# zynqBoard.net
KiCad netlist of a schematic drawn in Altium Designer
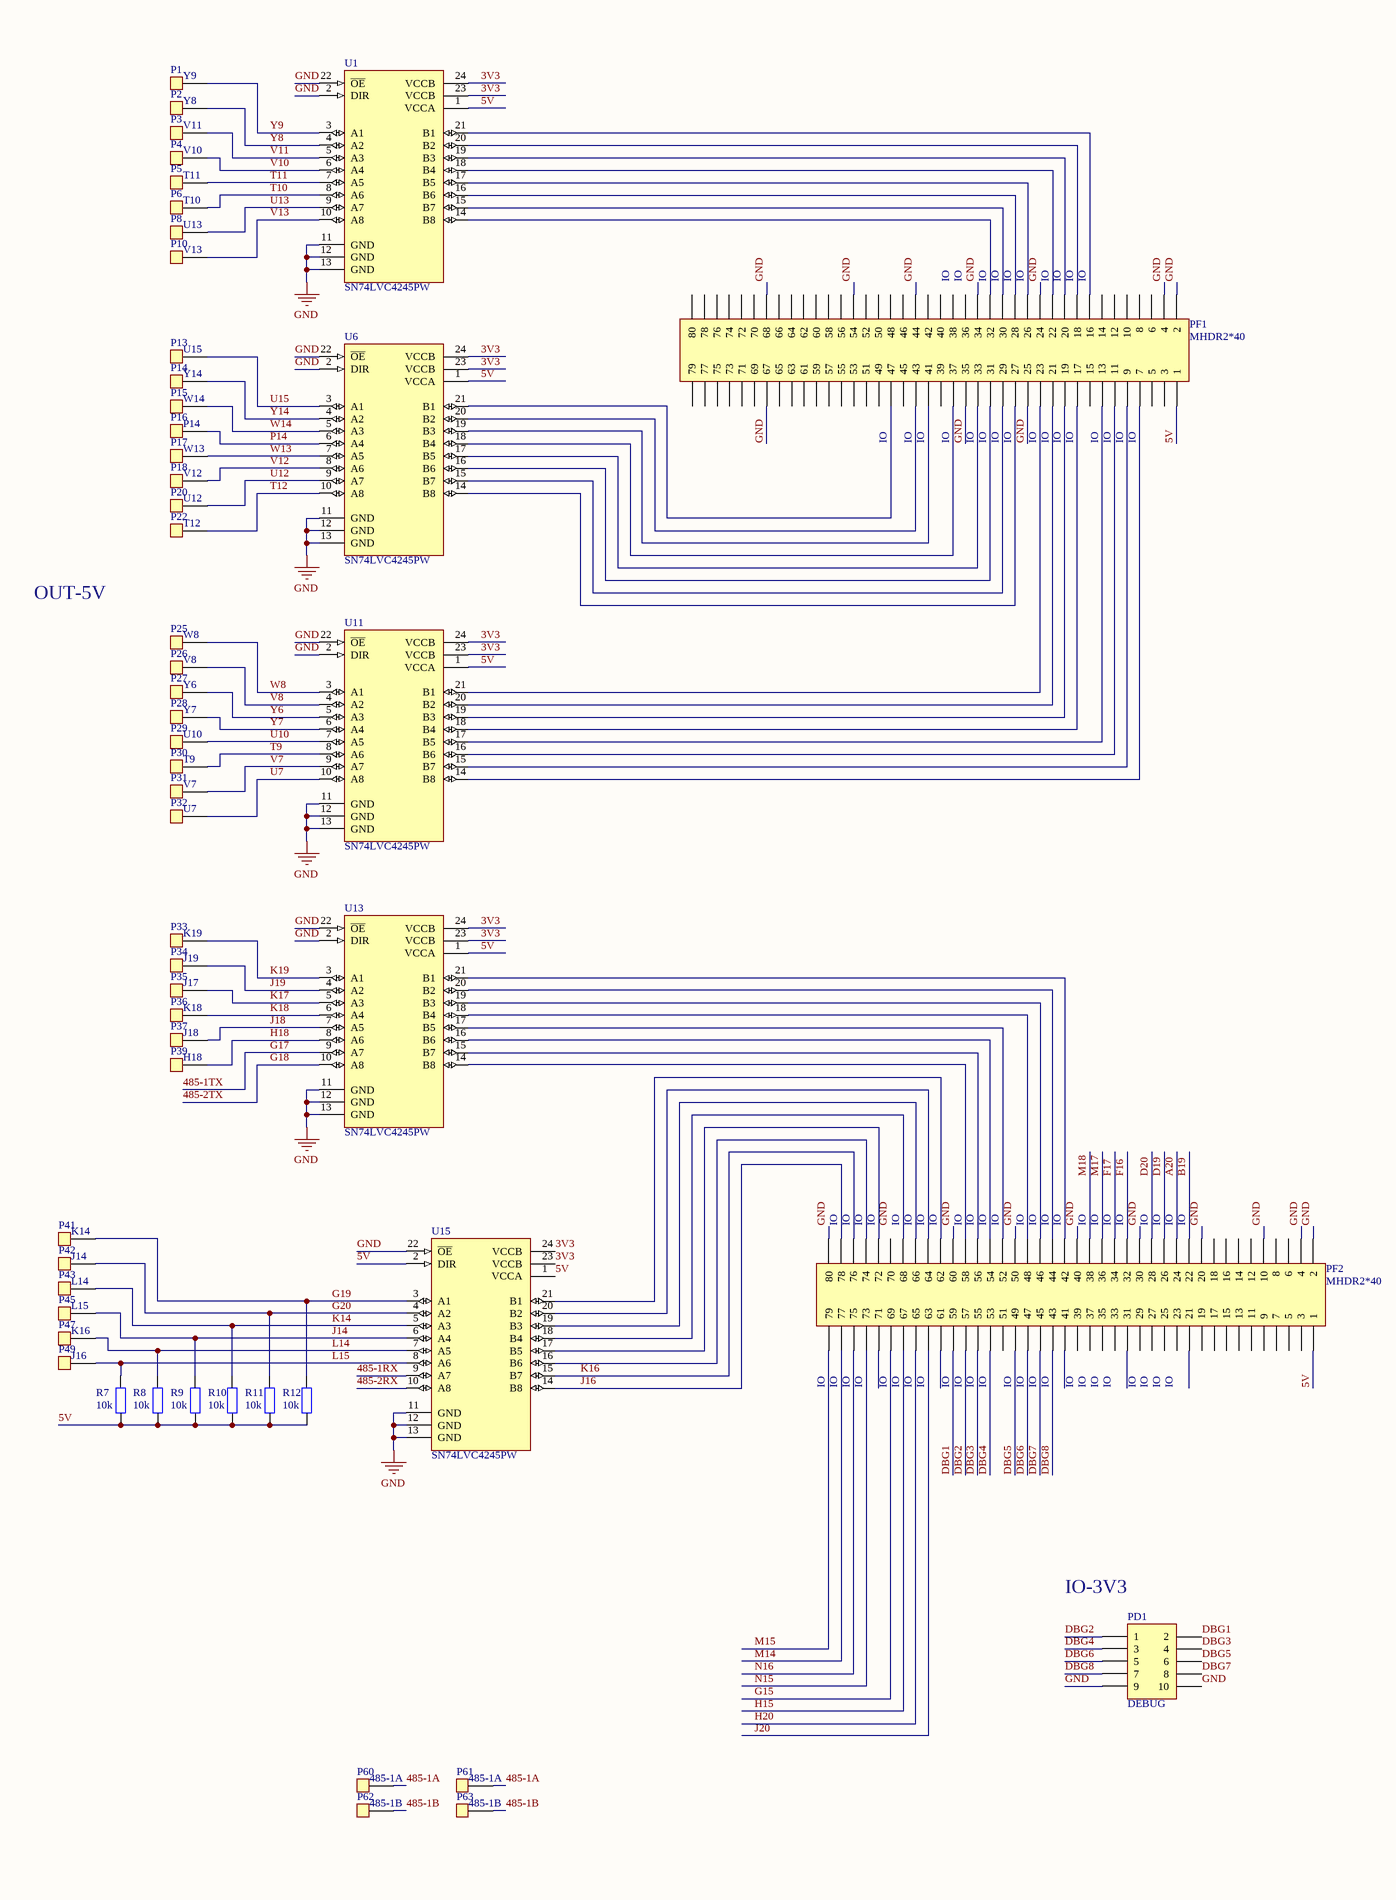
[diagram p0: zynqBoard.SchDoc, left]
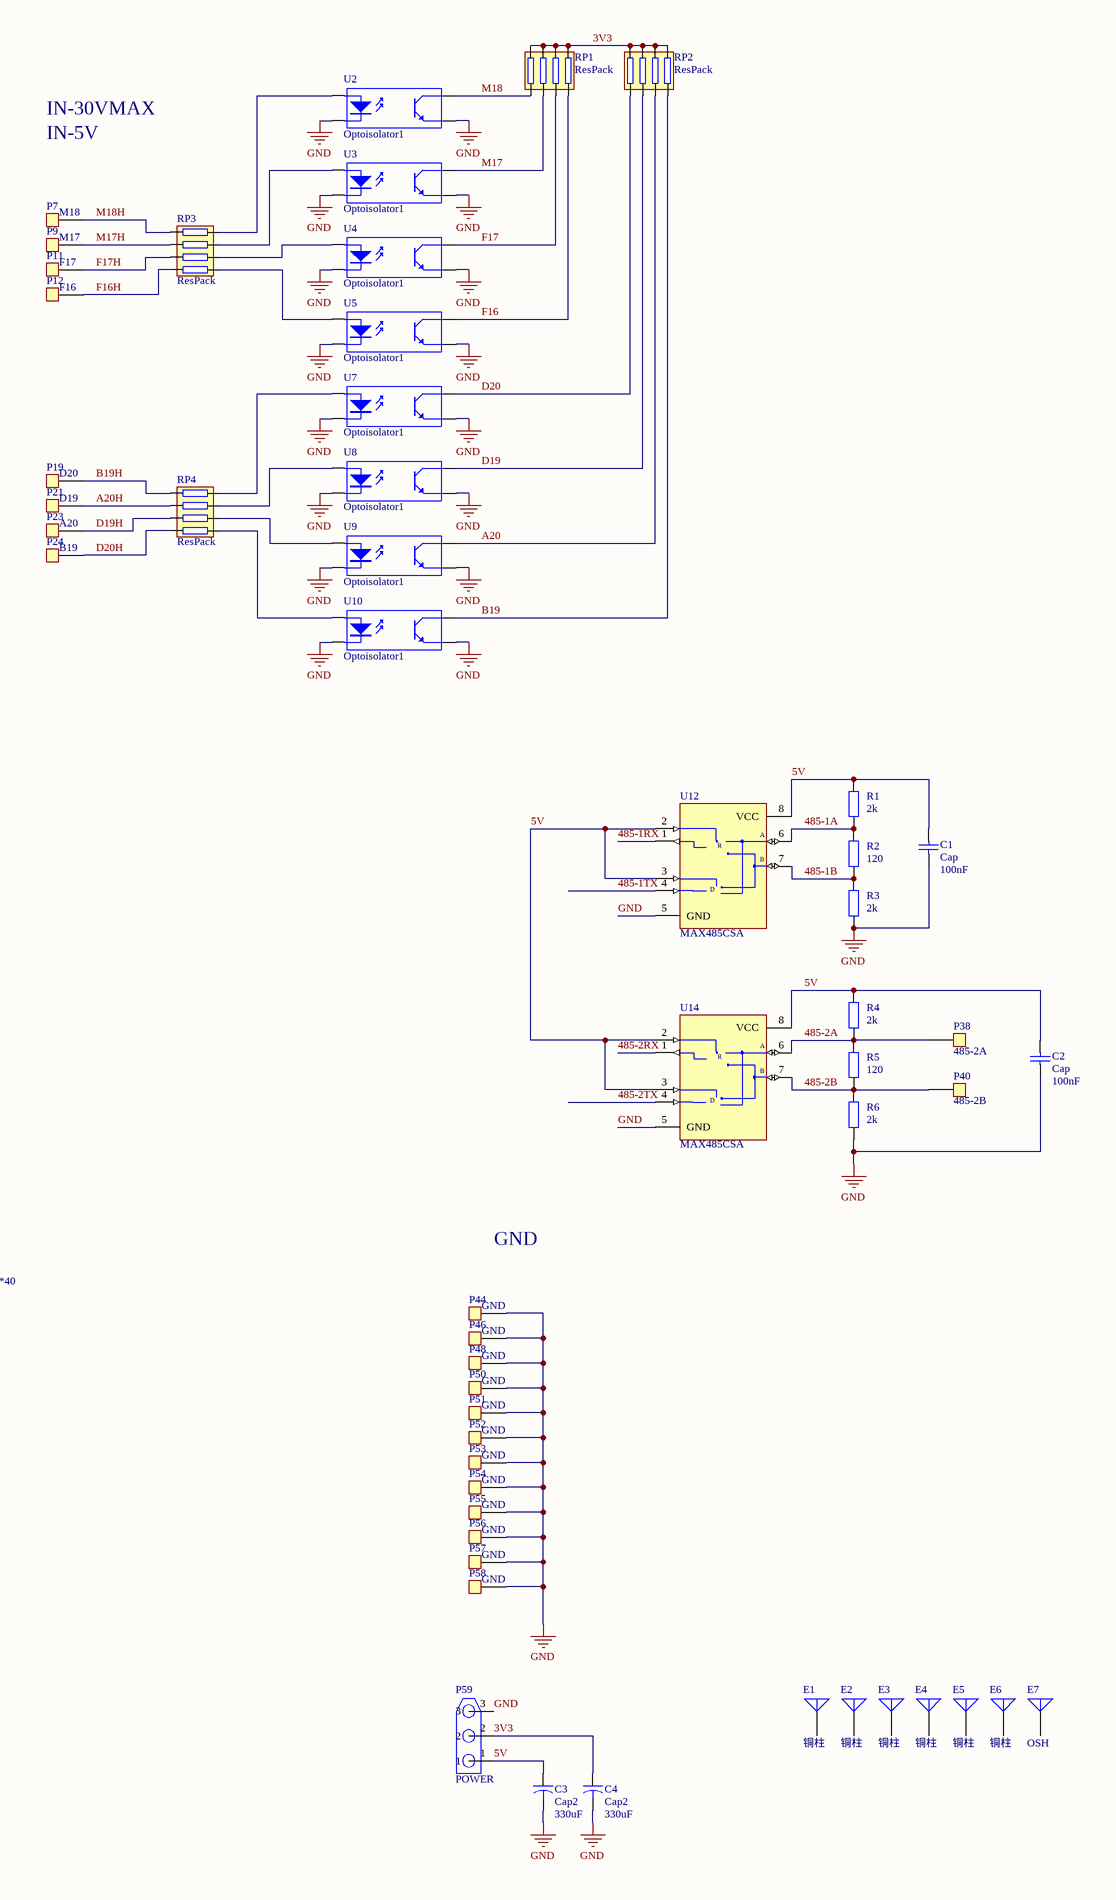
[diagram p1: zynqBoard.SchDoc, right]

(export (version "E")
  (design (tool "Eeschema 10.0.6"))
  (components
    (comp (ref "C1")
      (value "Cap")
      (footprint "1608[0603]big")
      (description "Capacitor")
      (fields (field (name "ALTIUM_VALUE") "100nF") (field (name "PUBLISHER") "Altium Limited"))
      (libsource (lib "Miscellaneous Devices") (part "Cap"))
    )
    (comp (ref "C2")
      (value "Cap")
      (footprint "1608[0603]big")
      (description "Capacitor")
      (fields (field (name "ALTIUM_VALUE") "100nF") (field (name "PUBLISHER") "Altium Limited"))
      (libsource (lib "Miscellaneous Devices") (part "Cap"))
    )
    (comp (ref "C3")
      (value "Cap2")
      (footprint "AVX_D_7343-31")
      (description "Capacitor")
      (fields (field (name "ALTIUM_VALUE") "330uF") (field (name "PUBLISHER") "Altium Limited"))
      (libsource (lib "Miscellaneous Devices") (part "Cap2"))
    )
    (comp (ref "C4")
      (value "Cap2")
      (footprint "AVX_D_7343-31")
      (description "Capacitor")
      (fields (field (name "ALTIUM_VALUE") "330uF") (field (name "PUBLISHER") "Altium Limited"))
      (libsource (lib "Miscellaneous Devices") (part "Cap2"))
    )
    (comp (ref "E1")
      (value "铜柱")
      (footprint "铜柱孔")
      (description "Generic Antenna")
      (fields (field (name "PUBLISHER") "Altium Limited"))
      (libsource (lib "Miscellaneous Devices") (part "Antenna"))
    )
    (comp (ref "E2")
      (value "铜柱")
      (footprint "铜柱孔")
      (description "Generic Antenna")
      (fields (field (name "PUBLISHER") "Altium Limited"))
      (libsource (lib "Miscellaneous Devices") (part "Antenna"))
    )
    (comp (ref "E3")
      (value "铜柱")
      (footprint "铜柱孔")
      (description "Generic Antenna")
      (fields (field (name "PUBLISHER") "Altium Limited"))
      (libsource (lib "Miscellaneous Devices") (part "Antenna"))
    )
    (comp (ref "E4")
      (value "铜柱")
      (footprint "铜柱孔")
      (description "Generic Antenna")
      (fields (field (name "PUBLISHER") "Altium Limited"))
      (libsource (lib "Miscellaneous Devices") (part "Antenna"))
    )
    (comp (ref "E5")
      (value "铜柱")
      (footprint "铜柱孔")
      (description "Generic Antenna")
      (fields (field (name "PUBLISHER") "Altium Limited"))
      (libsource (lib "Miscellaneous Devices") (part "Antenna"))
    )
    (comp (ref "E6")
      (value "铜柱")
      (footprint "铜柱孔")
      (description "Generic Antenna")
      (fields (field (name "PUBLISHER") "Altium Limited"))
      (libsource (lib "Miscellaneous Devices") (part "Antenna"))
    )
    (comp (ref "E7")
      (value "OSH")
      (footprint "OPENSOURECE")
      (description "Generic Antenna")
      (fields (field (name "PUBLISHER") "Altium Limited"))
      (libsource (lib "Miscellaneous Devices") (part "Antenna"))
    )
    (comp (ref "P1")
      (value "Y9")
      (footprint "HEADER_5.08MM_SINGLE")
      (libsource (lib "Schlib1") (part "conn"))
    )
    (comp (ref "P2")
      (value "Y8")
      (footprint "HEADER_5.08MM_SINGLE")
      (libsource (lib "Schlib1") (part "conn"))
    )
    (comp (ref "P3")
      (value "V11")
      (footprint "HEADER_5.08MM_SINGLE")
      (libsource (lib "Schlib1") (part "conn"))
    )
    (comp (ref "P4")
      (value "V10")
      (footprint "HEADER_5.08MM_SINGLE")
      (libsource (lib "Schlib1") (part "conn"))
    )
    (comp (ref "P5")
      (value "T11")
      (footprint "HEADER_5.08MM_SINGLE")
      (libsource (lib "Schlib1") (part "conn"))
    )
    (comp (ref "P6")
      (value "T10")
      (footprint "HEADER_5.08MM_SINGLE")
      (libsource (lib "Schlib1") (part "conn"))
    )
    (comp (ref "P7")
      (value "M18")
      (footprint "HEADER_5.08MM_SINGLE")
      (libsource (lib "Schlib1") (part "conn"))
    )
    (comp (ref "P8")
      (value "U13")
      (footprint "HEADER_5.08MM_SINGLE")
      (libsource (lib "Schlib1") (part "conn"))
    )
    (comp (ref "P9")
      (value "M17")
      (footprint "HEADER_5.08MM_SINGLE")
      (libsource (lib "Schlib1") (part "conn"))
    )
    (comp (ref "P10")
      (value "V13")
      (footprint "HEADER_5.08MM_SINGLE")
      (libsource (lib "Schlib1") (part "conn"))
    )
    (comp (ref "P11")
      (value "F17")
      (footprint "HEADER_5.08MM_SINGLE")
      (libsource (lib "Schlib1") (part "conn"))
    )
    (comp (ref "P12")
      (value "F16")
      (footprint "HEADER_5.08MM_SINGLE")
      (libsource (lib "Schlib1") (part "conn"))
    )
    (comp (ref "P13")
      (value "U15")
      (footprint "HEADER_5.08MM_SINGLE")
      (libsource (lib "Schlib1") (part "conn"))
    )
    (comp (ref "P14")
      (value "Y14")
      (footprint "HEADER_5.08MM_SINGLE")
      (libsource (lib "Schlib1") (part "conn"))
    )
    (comp (ref "P15")
      (value "W14")
      (footprint "HEADER_5.08MM_SINGLE")
      (libsource (lib "Schlib1") (part "conn"))
    )
    (comp (ref "P16")
      (value "P14")
      (footprint "HEADER_5.08MM_SINGLE")
      (libsource (lib "Schlib1") (part "conn"))
    )
    (comp (ref "P17")
      (value "W13")
      (footprint "HEADER_5.08MM_SINGLE")
      (libsource (lib "Schlib1") (part "conn"))
    )
    (comp (ref "P18")
      (value "V12")
      (footprint "HEADER_5.08MM_SINGLE")
      (libsource (lib "Schlib1") (part "conn"))
    )
    (comp (ref "P19")
      (value "D20")
      (footprint "HEADER_5.08MM_SINGLE")
      (libsource (lib "Schlib1") (part "conn"))
    )
    (comp (ref "P20")
      (value "U12")
      (footprint "HEADER_5.08MM_SINGLE")
      (libsource (lib "Schlib1") (part "conn"))
    )
    (comp (ref "P21")
      (value "D19")
      (footprint "HEADER_5.08MM_SINGLE")
      (libsource (lib "Schlib1") (part "conn"))
    )
    (comp (ref "P22")
      (value "T12")
      (footprint "HEADER_5.08MM_SINGLE")
      (libsource (lib "Schlib1") (part "conn"))
    )
    (comp (ref "P23")
      (value "A20")
      (footprint "HEADER_5.08MM_SINGLE")
      (libsource (lib "Schlib1") (part "conn"))
    )
    (comp (ref "P24")
      (value "B19")
      (footprint "HEADER_5.08MM_SINGLE")
      (libsource (lib "Schlib1") (part "conn"))
    )
    (comp (ref "P25")
      (value "W8")
      (footprint "HEADER_5.08MM_SINGLE")
      (libsource (lib "Schlib1") (part "conn"))
    )
    (comp (ref "P26")
      (value "V8")
      (footprint "HEADER_5.08MM_SINGLE")
      (libsource (lib "Schlib1") (part "conn"))
    )
    (comp (ref "P27")
      (value "Y6")
      (footprint "HEADER_5.08MM_SINGLE")
      (libsource (lib "Schlib1") (part "conn"))
    )
    (comp (ref "P28")
      (value "Y7")
      (footprint "HEADER_5.08MM_SINGLE")
      (libsource (lib "Schlib1") (part "conn"))
    )
    (comp (ref "P29")
      (value "U10")
      (footprint "HEADER_5.08MM_SINGLE")
      (libsource (lib "Schlib1") (part "conn"))
    )
    (comp (ref "P30")
      (value "T9")
      (footprint "HEADER_5.08MM_SINGLE")
      (libsource (lib "Schlib1") (part "conn"))
    )
    (comp (ref "P31")
      (value "V7")
      (footprint "HEADER_5.08MM_SINGLE")
      (libsource (lib "Schlib1") (part "conn"))
    )
    (comp (ref "P32")
      (value "U7")
      (footprint "HEADER_5.08MM_SINGLE")
      (libsource (lib "Schlib1") (part "conn"))
    )
    (comp (ref "P33")
      (value "K19")
      (footprint "HEADER_5.08MM_SINGLE")
      (libsource (lib "Schlib1") (part "conn"))
    )
    (comp (ref "P34")
      (value "J19")
      (footprint "HEADER_5.08MM_SINGLE")
      (libsource (lib "Schlib1") (part "conn"))
    )
    (comp (ref "P35")
      (value "J17")
      (footprint "HEADER_5.08MM_SINGLE")
      (libsource (lib "Schlib1") (part "conn"))
    )
    (comp (ref "P36")
      (value "K18")
      (footprint "HEADER_5.08MM_SINGLE")
      (libsource (lib "Schlib1") (part "conn"))
    )
    (comp (ref "P37")
      (value "J18")
      (footprint "HEADER_5.08MM_SINGLE")
      (libsource (lib "Schlib1") (part "conn"))
    )
    (comp (ref "P38")
      (value "485-2A")
      (footprint "HEADER_5.08MM_SINGLE")
      (libsource (lib "") (part "conn_1"))
    )
    (comp (ref "P39")
      (value "H18")
      (footprint "HEADER_5.08MM_SINGLE")
      (libsource (lib "Schlib1") (part "conn"))
    )
    (comp (ref "P40")
      (value "485-2B")
      (footprint "HEADER_5.08MM_SINGLE")
      (libsource (lib "") (part "conn_1"))
    )
    (comp (ref "P41")
      (value "K14")
      (footprint "HEADER_5.08MM_SINGLE")
      (libsource (lib "Schlib1") (part "conn"))
    )
    (comp (ref "P42")
      (value "J14")
      (footprint "HEADER_5.08MM_SINGLE")
      (libsource (lib "Schlib1") (part "conn"))
    )
    (comp (ref "P43")
      (value "L14")
      (footprint "HEADER_5.08MM_SINGLE")
      (libsource (lib "Schlib1") (part "conn"))
    )
    (comp (ref "P44")
      (value "GND")
      (footprint "HEADER_5.08MM_SINGLE")
      (libsource (lib "Schlib1") (part "conn"))
    )
    (comp (ref "P45")
      (value "L15")
      (footprint "HEADER_5.08MM_SINGLE")
      (libsource (lib "Schlib1") (part "conn"))
    )
    (comp (ref "P46")
      (value "GND")
      (footprint "HEADER_5.08MM_SINGLE")
      (libsource (lib "Schlib1") (part "conn"))
    )
    (comp (ref "P47")
      (value "K16")
      (footprint "HEADER_5.08MM_SINGLE")
      (libsource (lib "Schlib1") (part "conn"))
    )
    (comp (ref "P48")
      (value "GND")
      (footprint "HEADER_5.08MM_SINGLE")
      (libsource (lib "Schlib1") (part "conn"))
    )
    (comp (ref "P49")
      (value "J16")
      (footprint "HEADER_5.08MM_SINGLE")
      (libsource (lib "Schlib1") (part "conn"))
    )
    (comp (ref "P50")
      (value "GND")
      (footprint "HEADER_5.08MM_SINGLE")
      (libsource (lib "Schlib1") (part "conn"))
    )
    (comp (ref "P51")
      (value "GND")
      (footprint "HEADER_5.08MM_SINGLE")
      (libsource (lib "Schlib1") (part "conn"))
    )
    (comp (ref "P52")
      (value "GND")
      (footprint "HEADER_5.08MM_SINGLE")
      (libsource (lib "Schlib1") (part "conn"))
    )
    (comp (ref "P53")
      (value "GND")
      (footprint "HEADER_5.08MM_SINGLE")
      (libsource (lib "Schlib1") (part "conn"))
    )
    (comp (ref "P54")
      (value "GND")
      (footprint "HEADER_5.08MM_SINGLE")
      (libsource (lib "Schlib1") (part "conn"))
    )
    (comp (ref "P55")
      (value "GND")
      (footprint "HEADER_5.08MM_SINGLE")
      (libsource (lib "Schlib1") (part "conn"))
    )
    (comp (ref "P56")
      (value "GND")
      (footprint "HEADER_5.08MM_SINGLE")
      (libsource (lib "Schlib1") (part "conn"))
    )
    (comp (ref "P57")
      (value "GND")
      (footprint "HEADER_5.08MM_SINGLE")
      (libsource (lib "Schlib1") (part "conn"))
    )
    (comp (ref "P58")
      (value "GND")
      (footprint "HEADER_5.08MM_SINGLE")
      (libsource (lib "Schlib1") (part "conn"))
    )
    (comp (ref "P59")
      (value "POWER")
      (footprint "MR30")
      (description "XT30-3P")
      (libsource (lib "Schlib1") (part "XT30-3P"))
    )
    (comp (ref "P60")
      (value "485-1A")
      (footprint "HEADER_5.08MM_SINGLE")
      (libsource (lib "Schlib1") (part "conn"))
    )
    (comp (ref "P61")
      (value "485-1A")
      (footprint "HEADER_5.08MM_SINGLE")
      (libsource (lib "Schlib1") (part "conn"))
    )
    (comp (ref "P62")
      (value "485-1B")
      (footprint "HEADER_5.08MM_SINGLE")
      (libsource (lib "Schlib1") (part "conn"))
    )
    (comp (ref "P63")
      (value "485-1B")
      (footprint "HEADER_5.08MM_SINGLE")
      (libsource (lib "Schlib1") (part "conn"))
    )
    (comp (ref "PD1")
      (value "DEBUG")
      (footprint "HDR2X5")
      (description "Header, 5-Pin, Dual row")
      (fields (field (name "PUBLISHER") "Altium Limited"))
      (libsource (lib "Miscellaneous Connectors") (part "Header 5X2"))
    )
    (comp (ref "PF1")
      (value "MHDR2*40")
      (footprint "sbMHeader2*40")
      (libsource (lib "Schlib1") (part "MHDR2*40"))
    )
    (comp (ref "PF2")
      (value "MHDR2*40")
      (footprint "sbMHeader2*40")
      (libsource (lib "Schlib1") (part "MHDR2*40"))
    )
    (comp (ref "R1")
      (value "2k")
      (footprint "1608[0603]big")
      (description "Resistor")
      (fields (field (name "Comment") "Res2") (field (name "PUBLISHER") "Altium Limited"))
      (libsource (lib "Miscellaneous Devices") (part "Res2"))
    )
    (comp (ref "R2")
      (value "120")
      (footprint "1608[0603]big")
      (description "Resistor")
      (fields (field (name "Comment") "Res2") (field (name "PUBLISHER") "Altium Limited"))
      (libsource (lib "Miscellaneous Devices") (part "Res2"))
    )
    (comp (ref "R3")
      (value "2k")
      (footprint "1608[0603]big")
      (description "Resistor")
      (fields (field (name "Comment") "Res2") (field (name "PUBLISHER") "Altium Limited"))
      (libsource (lib "Miscellaneous Devices") (part "Res2"))
    )
    (comp (ref "R4")
      (value "2k")
      (footprint "1608[0603]big")
      (description "Resistor")
      (fields (field (name "Comment") "Res2") (field (name "PUBLISHER") "Altium Limited"))
      (libsource (lib "Miscellaneous Devices") (part "Res2"))
    )
    (comp (ref "R5")
      (value "120")
      (footprint "1608[0603]big")
      (description "Resistor")
      (fields (field (name "Comment") "Res2") (field (name "PUBLISHER") "Altium Limited"))
      (libsource (lib "Miscellaneous Devices") (part "Res2"))
    )
    (comp (ref "R6")
      (value "2k")
      (footprint "1608[0603]big")
      (description "Resistor")
      (fields (field (name "Comment") "Res2") (field (name "PUBLISHER") "Altium Limited"))
      (libsource (lib "Miscellaneous Devices") (part "Res2"))
    )
    (comp (ref "R7")
      (value "10k")
      (footprint "1608[0603]big")
      (description "Resistor")
      (fields (field (name "PUBLISHER") "Altium Limited"))
      (libsource (lib "Miscellaneous Devices") (part "Res2"))
    )
    (comp (ref "R8")
      (value "10k")
      (footprint "1608[0603]big")
      (description "Resistor")
      (fields (field (name "PUBLISHER") "Altium Limited"))
      (libsource (lib "Miscellaneous Devices") (part "Res2"))
    )
    (comp (ref "R9")
      (value "10k")
      (footprint "1608[0603]big")
      (description "Resistor")
      (fields (field (name "PUBLISHER") "Altium Limited"))
      (libsource (lib "Miscellaneous Devices") (part "Res2"))
    )
    (comp (ref "R10")
      (value "10k")
      (footprint "1608[0603]big")
      (description "Resistor")
      (fields (field (name "PUBLISHER") "Altium Limited"))
      (libsource (lib "Miscellaneous Devices") (part "Res2"))
    )
    (comp (ref "R11")
      (value "10k")
      (footprint "1608[0603]big")
      (description "Resistor")
      (fields (field (name "PUBLISHER") "Altium Limited"))
      (libsource (lib "Miscellaneous Devices") (part "Res2"))
    )
    (comp (ref "R12")
      (value "10k")
      (footprint "1608[0603]big")
      (description "Resistor")
      (fields (field (name "PUBLISHER") "Altium Limited"))
      (libsource (lib "Miscellaneous Devices") (part "Res2"))
    )
    (comp (ref "RP1")
      (value "ResPack")
      (footprint "LC-0603_Rx4")
      (libsource (lib "Schlib1") (part "ResPackx4"))
    )
    (comp (ref "RP2")
      (value "ResPack")
      (footprint "LC-0603_Rx4")
      (libsource (lib "Schlib1") (part "ResPackx4"))
    )
    (comp (ref "RP3") (value "ResPack") (footprint "LC-0603_Rx4") (libsource (lib "") (part "ResPackx4_1")))
    (comp (ref "RP4") (value "ResPack") (footprint "LC-0603_Rx4") (libsource (lib "") (part "ResPackx4_1")))
    (comp (ref "U1")
      (value "SN74LVC4245PW")
      (footprint "PW024")
      (description "Octal Bus Transceiver and 3.3-V to 5-V Shifter with 3-State Outputs")
      (fields (field (name "PUBLISHER") "Altium Limited"))
      (libsource (lib "TI Interface 8-Bit Line Transceiver") (part "SN74LVC4245PW"))
    )
    (comp (ref "U2")
      (value "Optoisolator1")
      (footprint "LC-SMD-4")
      (description "4-Pin Phototransistor Optocoupler")
      (fields (field (name "PUBLISHER") "Altium Limited"))
      (libsource (lib "Miscellaneous Devices") (part "Optoisolator1"))
    )
    (comp (ref "U3")
      (value "Optoisolator1")
      (footprint "LC-SMD-4")
      (description "4-Pin Phototransistor Optocoupler")
      (fields (field (name "PUBLISHER") "Altium Limited"))
      (libsource (lib "Miscellaneous Devices") (part "Optoisolator1"))
    )
    (comp (ref "U4")
      (value "Optoisolator1")
      (footprint "LC-SMD-4")
      (description "4-Pin Phototransistor Optocoupler")
      (fields (field (name "PUBLISHER") "Altium Limited"))
      (libsource (lib "Miscellaneous Devices") (part "Optoisolator1"))
    )
    (comp (ref "U5")
      (value "Optoisolator1")
      (footprint "LC-SMD-4")
      (description "4-Pin Phototransistor Optocoupler")
      (fields (field (name "PUBLISHER") "Altium Limited"))
      (libsource (lib "Miscellaneous Devices") (part "Optoisolator1"))
    )
    (comp (ref "U6")
      (value "SN74LVC4245PW")
      (footprint "PW024")
      (description "Octal Bus Transceiver and 3.3-V to 5-V Shifter with 3-State Outputs")
      (fields (field (name "PUBLISHER") "Altium Limited"))
      (libsource (lib "TI Interface 8-Bit Line Transceiver") (part "SN74LVC4245PW"))
    )
    (comp (ref "U7")
      (value "Optoisolator1")
      (footprint "LC-SMD-4")
      (description "4-Pin Phototransistor Optocoupler")
      (fields (field (name "PUBLISHER") "Altium Limited"))
      (libsource (lib "Miscellaneous Devices") (part "Optoisolator1"))
    )
    (comp (ref "U8")
      (value "Optoisolator1")
      (footprint "LC-SMD-4")
      (description "4-Pin Phototransistor Optocoupler")
      (fields (field (name "PUBLISHER") "Altium Limited"))
      (libsource (lib "Miscellaneous Devices") (part "Optoisolator1"))
    )
    (comp (ref "U9")
      (value "Optoisolator1")
      (footprint "LC-SMD-4")
      (description "4-Pin Phototransistor Optocoupler")
      (fields (field (name "PUBLISHER") "Altium Limited"))
      (libsource (lib "Miscellaneous Devices") (part "Optoisolator1"))
    )
    (comp (ref "U10")
      (value "Optoisolator1")
      (footprint "LC-SMD-4")
      (description "4-Pin Phototransistor Optocoupler")
      (fields (field (name "PUBLISHER") "Altium Limited"))
      (libsource (lib "Miscellaneous Devices") (part "Optoisolator1"))
    )
    (comp (ref "U11")
      (value "SN74LVC4245PW")
      (footprint "PW024")
      (description "Octal Bus Transceiver and 3.3-V to 5-V Shifter with 3-State Outputs")
      (fields (field (name "PUBLISHER") "Altium Limited"))
      (libsource (lib "TI Interface 8-Bit Line Transceiver") (part "SN74LVC4245PW"))
    )
    (comp (ref "U12")
      (value "MAX485CSA")
      (footprint "NSO8_N")
      (description "Low-Power, Slew-Rate-Limited RS-485/RS-422 Transceiver")
      (fields (field (name "PUBLISHER") "Altium Limited"))
      (libsource (lib "Maxim Communication Transceiver") (part "MAX485CSA"))
    )
    (comp (ref "U13")
      (value "SN74LVC4245PW")
      (footprint "PW024")
      (description "Octal Bus Transceiver and 3.3-V to 5-V Shifter with 3-State Outputs")
      (fields (field (name "PUBLISHER") "Altium Limited"))
      (libsource (lib "TI Interface 8-Bit Line Transceiver") (part "SN74LVC4245PW"))
    )
    (comp (ref "U14")
      (value "MAX485CSA")
      (footprint "NSO8_N")
      (description "Low-Power, Slew-Rate-Limited RS-485/RS-422 Transceiver")
      (fields (field (name "PUBLISHER") "Altium Limited"))
      (libsource (lib "Maxim Communication Transceiver") (part "MAX485CSA"))
    )
    (comp (ref "U15")
      (value "SN74LVC4245PW")
      (footprint "PW024")
      (description "Octal Bus Transceiver and 3.3-V to 5-V Shifter with 3-State Outputs")
      (fields (field (name "PUBLISHER") "Altium Limited"))
      (libsource (lib "TI Interface 8-Bit Line Transceiver") (part "SN74LVC4245PW"))
    )
  )
  (nets
    (net (code "1") (name "/3V3") (class "Default")
      (node (ref "C4") (pin "1") (pinfunction "1_1") (pintype "passive"))
      (node (ref "P59") (pin "2") (pinfunction "2_2") (pintype "passive"))
      (node (ref "RP1") (pin "5") (pinfunction "5_5") (pintype "passive"))
      (node (ref "RP1") (pin "6") (pinfunction "6_6") (pintype "passive"))
      (node (ref "RP1") (pin "7") (pinfunction "7_7") (pintype "passive"))
      (node (ref "RP1") (pin "8") (pinfunction "8_8") (pintype "passive"))
      (node (ref "RP2") (pin "5") (pinfunction "5_5") (pintype "passive"))
      (node (ref "RP2") (pin "6") (pinfunction "6_6") (pintype "passive"))
      (node (ref "RP2") (pin "7") (pinfunction "7_7") (pintype "passive"))
      (node (ref "RP2") (pin "8") (pinfunction "8_8") (pintype "passive"))
      (node (ref "U1") (pin "23") (pinfunction "VCCB_23") (pintype "power_in"))
      (node (ref "U1") (pin "24") (pinfunction "VCCB_24") (pintype "power_in"))
      (node (ref "U11") (pin "23") (pinfunction "VCCB_23") (pintype "power_in"))
      (node (ref "U11") (pin "24") (pinfunction "VCCB_24") (pintype "power_in"))
      (node (ref "U13") (pin "23") (pinfunction "VCCB_23") (pintype "power_in"))
      (node (ref "U13") (pin "24") (pinfunction "VCCB_24") (pintype "power_in"))
      (node (ref "U15") (pin "23") (pinfunction "VCCB_23") (pintype "power_in"))
      (node (ref "U15") (pin "24") (pinfunction "VCCB_24") (pintype "power_in"))
      (node (ref "U6") (pin "23") (pinfunction "VCCB_23") (pintype "power_in"))
      (node (ref "U6") (pin "24") (pinfunction "VCCB_24") (pintype "power_in"))
    )
    (net (code "2") (name "/5V") (class "Default")
      (node (ref "C1") (pin "2") (pinfunction "2_2") (pintype "passive"))
      (node (ref "C2") (pin "2") (pinfunction "2_2") (pintype "passive"))
      (node (ref "C3") (pin "1") (pinfunction "1_1") (pintype "passive"))
      (node (ref "P59") (pin "1") (pinfunction "1_1") (pintype "passive"))
      (node (ref "PF1") (pin "1") (pinfunction "1_1") (pintype "passive"))
      (node (ref "PF2") (pin "1") (pinfunction "1_1") (pintype "passive"))
      (node (ref "R1") (pin "2") (pinfunction "2_2") (pintype "passive"))
      (node (ref "R10") (pin "1") (pinfunction "1_1") (pintype "passive"))
      (node (ref "R11") (pin "1") (pinfunction "1_1") (pintype "passive"))
      (node (ref "R12") (pin "1") (pinfunction "1_1") (pintype "passive"))
      (node (ref "R4") (pin "2") (pinfunction "2_2") (pintype "passive"))
      (node (ref "R7") (pin "1") (pinfunction "1_1") (pintype "passive"))
      (node (ref "R8") (pin "1") (pinfunction "1_1") (pintype "passive"))
      (node (ref "R9") (pin "1") (pinfunction "1_1") (pintype "passive"))
      (node (ref "U1") (pin "1") (pinfunction "VCCA_1") (pintype "power_in"))
      (node (ref "U11") (pin "1") (pinfunction "VCCA_1") (pintype "power_in"))
      (node (ref "U12") (pin "2") (pinfunction "~{RE}_2") (pintype "input"))
      (node (ref "U12") (pin "3") (pinfunction "DE_3") (pintype "input"))
      (node (ref "U12") (pin "8") (pinfunction "VCC_8") (pintype "power_in"))
      (node (ref "U13") (pin "1") (pinfunction "VCCA_1") (pintype "power_in"))
      (node (ref "U14") (pin "2") (pinfunction "~{RE}_2") (pintype "input"))
      (node (ref "U14") (pin "3") (pinfunction "DE_3") (pintype "input"))
      (node (ref "U14") (pin "8") (pinfunction "VCC_8") (pintype "power_in"))
      (node (ref "U15") (pin "1") (pinfunction "VCCA_1") (pintype "power_in"))
      (node (ref "U15") (pin "2") (pinfunction "DIR_2") (pintype "input"))
      (node (ref "U6") (pin "1") (pinfunction "VCCA_1") (pintype "power_in"))
    )
    (net (code "3") (name "/485-1A") (class "Default")
      (node (ref "P60") (pin "1") (pinfunction "1_1") (pintype "passive"))
      (node (ref "P61") (pin "1") (pinfunction "1_1") (pintype "passive"))
      (node (ref "R1") (pin "1") (pinfunction "1_1") (pintype "passive"))
      (node (ref "R2") (pin "2") (pinfunction "2_2") (pintype "passive"))
      (node (ref "U12") (pin "6") (pinfunction "A_6") (pintype "bidirectional"))
    )
    (net (code "4") (name "/485-1B") (class "Default")
      (node (ref "P62") (pin "1") (pinfunction "1_1") (pintype "passive"))
      (node (ref "P63") (pin "1") (pinfunction "1_1") (pintype "passive"))
      (node (ref "R2") (pin "1") (pinfunction "1_1") (pintype "passive"))
      (node (ref "R3") (pin "2") (pinfunction "2_2") (pintype "passive"))
      (node (ref "U12") (pin "7") (pinfunction "B_7") (pintype "bidirectional"))
    )
    (net (code "5") (name "/485-1RX") (class "Default")
      (node (ref "U12") (pin "1") (pinfunction "RO_1") (pintype "output"))
      (node (ref "U15") (pin "9") (pinfunction "A7_9") (pintype "bidirectional"))
    )
    (net (code "6") (name "/485-1TX") (class "Default")
      (node (ref "U12") (pin "4") (pinfunction "DI_4") (pintype "input"))
      (node (ref "U13") (pin "9") (pinfunction "A7_9") (pintype "bidirectional"))
    )
    (net (code "7") (name "/485-2A") (class "Default")
      (node (ref "P38") (pin "1") (pinfunction "1_1") (pintype "passive"))
      (node (ref "R4") (pin "1") (pinfunction "1_1") (pintype "passive"))
      (node (ref "R5") (pin "2") (pinfunction "2_2") (pintype "passive"))
      (node (ref "U14") (pin "6") (pinfunction "A_6") (pintype "bidirectional"))
    )
    (net (code "8") (name "/485-2B") (class "Default")
      (node (ref "P40") (pin "1") (pinfunction "1_1") (pintype "passive"))
      (node (ref "R5") (pin "1") (pinfunction "1_1") (pintype "passive"))
      (node (ref "R6") (pin "2") (pinfunction "2_2") (pintype "passive"))
      (node (ref "U14") (pin "7") (pinfunction "B_7") (pintype "bidirectional"))
    )
    (net (code "9") (name "/485-2RX") (class "Default")
      (node (ref "U14") (pin "1") (pinfunction "RO_1") (pintype "output"))
      (node (ref "U15") (pin "10") (pinfunction "A8_10") (pintype "bidirectional"))
    )
    (net (code "10") (name "/485-2TX") (class "Default")
      (node (ref "U13") (pin "10") (pinfunction "A8_10") (pintype "bidirectional"))
      (node (ref "U14") (pin "4") (pinfunction "DI_4") (pintype "input"))
    )
    (net (code "11") (name "/A20") (class "Default")
      (node (ref "PF2") (pin "24") (pinfunction "24_24") (pintype "passive"))
      (node (ref "RP2") (pin "3") (pinfunction "3_3") (pintype "passive"))
      (node (ref "U9") (pin "4") (pinfunction "C_4") (pintype "passive"))
    )
    (net (code "12") (name "/A20H") (class "Default")
      (node (ref "P21") (pin "1") (pinfunction "1_1") (pintype "passive"))
      (node (ref "RP4") (pin "7") (pinfunction "7_7") (pintype "passive"))
    )
    (net (code "13") (name "/B19") (class "Default")
      (node (ref "PF2") (pin "22") (pinfunction "22_22") (pintype "passive"))
      (node (ref "RP2") (pin "4") (pinfunction "4_4") (pintype "passive"))
      (node (ref "U10") (pin "4") (pinfunction "C_4") (pintype "passive"))
    )
    (net (code "14") (name "/B19H") (class "Default")
      (node (ref "P19") (pin "1") (pinfunction "1_1") (pintype "passive"))
      (node (ref "RP4") (pin "8") (pinfunction "8_8") (pintype "passive"))
    )
    (net (code "15") (name "/D19") (class "Default")
      (node (ref "PF2") (pin "26") (pinfunction "26_26") (pintype "passive"))
      (node (ref "RP2") (pin "2") (pinfunction "2_2") (pintype "passive"))
      (node (ref "U8") (pin "4") (pinfunction "C_4") (pintype "passive"))
    )
    (net (code "16") (name "/D19H") (class "Default")
      (node (ref "P23") (pin "1") (pinfunction "1_1") (pintype "passive"))
      (node (ref "RP4") (pin "6") (pinfunction "6_6") (pintype "passive"))
    )
    (net (code "17") (name "/D20") (class "Default")
      (node (ref "PF2") (pin "28") (pinfunction "28_28") (pintype "passive"))
      (node (ref "RP2") (pin "1") (pinfunction "1_1") (pintype "passive"))
      (node (ref "U7") (pin "4") (pinfunction "C_4") (pintype "passive"))
    )
    (net (code "18") (name "/D20H") (class "Default")
      (node (ref "P24") (pin "1") (pinfunction "1_1") (pintype "passive"))
      (node (ref "RP4") (pin "5") (pinfunction "5_5") (pintype "passive"))
    )
    (net (code "19") (name "/DBG1") (class "Default")
      (node (ref "PD1") (pin "2") (pinfunction "2_2") (pintype "passive"))
      (node (ref "PF2") (pin "59") (pinfunction "59_59") (pintype "passive"))
    )
    (net (code "20") (name "/DBG2") (class "Default")
      (node (ref "PD1") (pin "1") (pinfunction "1_1") (pintype "passive"))
      (node (ref "PF2") (pin "57") (pinfunction "57_57") (pintype "passive"))
    )
    (net (code "21") (name "/DBG3") (class "Default")
      (node (ref "PD1") (pin "4") (pinfunction "4_4") (pintype "passive"))
      (node (ref "PF2") (pin "55") (pinfunction "55_55") (pintype "passive"))
    )
    (net (code "22") (name "/DBG4") (class "Default")
      (node (ref "PD1") (pin "3") (pinfunction "3_3") (pintype "passive"))
      (node (ref "PF2") (pin "53") (pinfunction "53_53") (pintype "passive"))
    )
    (net (code "23") (name "/DBG5") (class "Default")
      (node (ref "PD1") (pin "6") (pinfunction "6_6") (pintype "passive"))
      (node (ref "PF2") (pin "49") (pinfunction "49_49") (pintype "passive"))
    )
    (net (code "24") (name "/DBG6") (class "Default")
      (node (ref "PD1") (pin "5") (pinfunction "5_5") (pintype "passive"))
      (node (ref "PF2") (pin "47") (pinfunction "47_47") (pintype "passive"))
    )
    (net (code "25") (name "/DBG7") (class "Default")
      (node (ref "PD1") (pin "8") (pinfunction "8_8") (pintype "passive"))
      (node (ref "PF2") (pin "45") (pinfunction "45_45") (pintype "passive"))
    )
    (net (code "26") (name "/DBG8") (class "Default")
      (node (ref "PD1") (pin "7") (pinfunction "7_7") (pintype "passive"))
      (node (ref "PF2") (pin "43") (pinfunction "43_43") (pintype "passive"))
    )
    (net (code "27") (name "/F16") (class "Default")
      (node (ref "PF2") (pin "32") (pinfunction "32_32") (pintype "passive"))
      (node (ref "RP1") (pin "4") (pinfunction "4_4") (pintype "passive"))
      (node (ref "U5") (pin "4") (pinfunction "C_4") (pintype "passive"))
    )
    (net (code "28") (name "/F16H") (class "Default")
      (node (ref "P12") (pin "1") (pinfunction "1_1") (pintype "passive"))
      (node (ref "RP3") (pin "5") (pinfunction "5_5") (pintype "passive"))
    )
    (net (code "29") (name "/F17") (class "Default")
      (node (ref "PF2") (pin "34") (pinfunction "34_34") (pintype "passive"))
      (node (ref "RP1") (pin "3") (pinfunction "3_3") (pintype "passive"))
      (node (ref "U4") (pin "4") (pinfunction "C_4") (pintype "passive"))
    )
    (net (code "30") (name "/F17H") (class "Default")
      (node (ref "P11") (pin "1") (pinfunction "1_1") (pintype "passive"))
      (node (ref "RP3") (pin "6") (pinfunction "6_6") (pintype "passive"))
    )
    (net (code "31") (name "/G15") (class "Default")
      (node (ref "PF2") (pin "69") (pinfunction "69_69") (pintype "passive"))
    )
    (net (code "32") (name "/G19") (class "Default")
      (node (ref "P41") (pin "1") (pinfunction "1_1") (pintype "passive"))
      (node (ref "R12") (pin "2") (pinfunction "2_2") (pintype "passive"))
      (node (ref "U15") (pin "3") (pinfunction "A1_3") (pintype "bidirectional"))
    )
    (net (code "33") (name "/G20") (class "Default")
      (node (ref "P42") (pin "1") (pinfunction "1_1") (pintype "passive"))
      (node (ref "R11") (pin "2") (pinfunction "2_2") (pintype "passive"))
      (node (ref "U15") (pin "4") (pinfunction "A2_4") (pintype "bidirectional"))
    )
    (net (code "34") (name "/H15") (class "Default")
      (node (ref "PF2") (pin "67") (pinfunction "67_67") (pintype "passive"))
    )
    (net (code "35") (name "/H18") (class "Default")
      (node (ref "P39") (pin "1") (pinfunction "1_1") (pintype "passive"))
      (node (ref "U13") (pin "8") (pinfunction "A6_8") (pintype "bidirectional"))
    )
    (net (code "36") (name "/H20") (class "Default")
      (node (ref "PF2") (pin "65") (pinfunction "65_65") (pintype "passive"))
    )
    (net (code "37") (name "/J14") (class "Default")
      (node (ref "P45") (pin "1") (pinfunction "1_1") (pintype "passive"))
      (node (ref "R9") (pin "2") (pinfunction "2_2") (pintype "passive"))
      (node (ref "U15") (pin "6") (pinfunction "A4_6") (pintype "bidirectional"))
    )
    (net (code "38") (name "/J16") (class "Default")
      (node (ref "PF2") (pin "78") (pinfunction "78_78") (pintype "passive"))
      (node (ref "U15") (pin "14") (pinfunction "B8_14") (pintype "bidirectional"))
    )
    (net (code "39") (name "/J18") (class "Default")
      (node (ref "P37") (pin "1") (pinfunction "1_1") (pintype "passive"))
      (node (ref "U13") (pin "7") (pinfunction "A5_7") (pintype "bidirectional"))
    )
    (net (code "40") (name "/J19") (class "Default")
      (node (ref "P34") (pin "1") (pinfunction "1_1") (pintype "passive"))
      (node (ref "U13") (pin "4") (pinfunction "A2_4") (pintype "bidirectional"))
    )
    (net (code "41") (name "/J20") (class "Default")
      (node (ref "PF2") (pin "63") (pinfunction "63_63") (pintype "passive"))
    )
    (net (code "42") (name "/K14") (class "Default")
      (node (ref "P43") (pin "1") (pinfunction "1_1") (pintype "passive"))
      (node (ref "R10") (pin "2") (pinfunction "2_2") (pintype "passive"))
      (node (ref "U15") (pin "5") (pinfunction "A3_5") (pintype "bidirectional"))
    )
    (net (code "43") (name "/K16") (class "Default")
      (node (ref "PF2") (pin "76") (pinfunction "76_76") (pintype "passive"))
      (node (ref "U15") (pin "15") (pinfunction "B7_15") (pintype "bidirectional"))
    )
    (net (code "44") (name "/K17") (class "Default")
      (node (ref "P35") (pin "1") (pinfunction "1_1") (pintype "passive"))
      (node (ref "U13") (pin "5") (pinfunction "A3_5") (pintype "bidirectional"))
    )
    (net (code "45") (name "/K18") (class "Default")
      (node (ref "P36") (pin "1") (pinfunction "1_1") (pintype "passive"))
      (node (ref "U13") (pin "6") (pinfunction "A4_6") (pintype "bidirectional"))
    )
    (net (code "46") (name "/K19") (class "Default")
      (node (ref "P33") (pin "1") (pinfunction "1_1") (pintype "passive"))
      (node (ref "U13") (pin "3") (pinfunction "A1_3") (pintype "bidirectional"))
    )
    (net (code "47") (name "/L14") (class "Default")
      (node (ref "P47") (pin "1") (pinfunction "1_1") (pintype "passive"))
      (node (ref "R8") (pin "2") (pinfunction "2_2") (pintype "passive"))
      (node (ref "U15") (pin "7") (pinfunction "A5_7") (pintype "bidirectional"))
    )
    (net (code "48") (name "/L15") (class "Default")
      (node (ref "P49") (pin "1") (pinfunction "1_1") (pintype "passive"))
      (node (ref "R7") (pin "2") (pinfunction "2_2") (pintype "passive"))
      (node (ref "U15") (pin "8") (pinfunction "A6_8") (pintype "bidirectional"))
    )
    (net (code "49") (name "/M14") (class "Default")
      (node (ref "PF2") (pin "77") (pinfunction "77_77") (pintype "passive"))
    )
    (net (code "50") (name "/M15") (class "Default")
      (node (ref "PF2") (pin "79") (pinfunction "79_79") (pintype "passive"))
    )
    (net (code "51") (name "/M17") (class "Default")
      (node (ref "PF2") (pin "36") (pinfunction "36_36") (pintype "passive"))
      (node (ref "RP1") (pin "2") (pinfunction "2_2") (pintype "passive"))
      (node (ref "U3") (pin "4") (pinfunction "C_4") (pintype "passive"))
    )
    (net (code "52") (name "/M17H") (class "Default")
      (node (ref "P9") (pin "1") (pinfunction "1_1") (pintype "passive"))
      (node (ref "RP3") (pin "7") (pinfunction "7_7") (pintype "passive"))
    )
    (net (code "53") (name "/M18") (class "Default")
      (node (ref "PF2") (pin "38") (pinfunction "38_38") (pintype "passive"))
      (node (ref "RP1") (pin "1") (pinfunction "1_1") (pintype "passive"))
      (node (ref "U2") (pin "4") (pinfunction "C_4") (pintype "passive"))
    )
    (net (code "54") (name "/M18H") (class "Default")
      (node (ref "P7") (pin "1") (pinfunction "1_1") (pintype "passive"))
      (node (ref "RP3") (pin "8") (pinfunction "8_8") (pintype "passive"))
    )
    (net (code "55") (name "/N15") (class "Default")
      (node (ref "PF2") (pin "73") (pinfunction "73_73") (pintype "passive"))
    )
    (net (code "56") (name "/N16") (class "Default")
      (node (ref "PF2") (pin "75") (pinfunction "75_75") (pintype "passive"))
    )
    (net (code "57") (name "/P14") (class "Default")
      (node (ref "P16") (pin "1") (pinfunction "1_1") (pintype "passive"))
      (node (ref "U6") (pin "6") (pinfunction "A4_6") (pintype "bidirectional"))
    )
    (net (code "58") (name "/T9") (class "Default")
      (node (ref "P30") (pin "1") (pinfunction "1_1") (pintype "passive"))
      (node (ref "U11") (pin "8") (pinfunction "A6_8") (pintype "bidirectional"))
    )
    (net (code "59") (name "/T10") (class "Default")
      (node (ref "P6") (pin "1") (pinfunction "1_1") (pintype "passive"))
      (node (ref "U1") (pin "8") (pinfunction "A6_8") (pintype "bidirectional"))
    )
    (net (code "60") (name "/T11") (class "Default")
      (node (ref "P5") (pin "1") (pinfunction "1_1") (pintype "passive"))
      (node (ref "U1") (pin "7") (pinfunction "A5_7") (pintype "bidirectional"))
    )
    (net (code "61") (name "/T12") (class "Default")
      (node (ref "P22") (pin "1") (pinfunction "1_1") (pintype "passive"))
      (node (ref "U6") (pin "10") (pinfunction "A8_10") (pintype "bidirectional"))
    )
    (net (code "62") (name "/U7") (class "Default")
      (node (ref "P32") (pin "1") (pinfunction "1_1") (pintype "passive"))
      (node (ref "U11") (pin "10") (pinfunction "A8_10") (pintype "bidirectional"))
    )
    (net (code "63") (name "/U10") (class "Default")
      (node (ref "P29") (pin "1") (pinfunction "1_1") (pintype "passive"))
      (node (ref "U11") (pin "7") (pinfunction "A5_7") (pintype "bidirectional"))
    )
    (net (code "64") (name "/U12") (class "Default")
      (node (ref "P20") (pin "1") (pinfunction "1_1") (pintype "passive"))
      (node (ref "U6") (pin "9") (pinfunction "A7_9") (pintype "bidirectional"))
    )
    (net (code "65") (name "/U13") (class "Default")
      (node (ref "P8") (pin "1") (pinfunction "1_1") (pintype "passive"))
      (node (ref "U1") (pin "9") (pinfunction "A7_9") (pintype "bidirectional"))
    )
    (net (code "66") (name "/U15") (class "Default")
      (node (ref "P13") (pin "1") (pinfunction "1_1") (pintype "passive"))
      (node (ref "U6") (pin "3") (pinfunction "A1_3") (pintype "bidirectional"))
    )
    (net (code "67") (name "/V7") (class "Default")
      (node (ref "P31") (pin "1") (pinfunction "1_1") (pintype "passive"))
      (node (ref "U11") (pin "9") (pinfunction "A7_9") (pintype "bidirectional"))
    )
    (net (code "68") (name "/V8") (class "Default")
      (node (ref "P26") (pin "1") (pinfunction "1_1") (pintype "passive"))
      (node (ref "U11") (pin "4") (pinfunction "A2_4") (pintype "bidirectional"))
    )
    (net (code "69") (name "/V10") (class "Default")
      (node (ref "P4") (pin "1") (pinfunction "1_1") (pintype "passive"))
      (node (ref "U1") (pin "6") (pinfunction "A4_6") (pintype "bidirectional"))
    )
    (net (code "70") (name "/V11") (class "Default")
      (node (ref "P3") (pin "1") (pinfunction "1_1") (pintype "passive"))
      (node (ref "U1") (pin "5") (pinfunction "A3_5") (pintype "bidirectional"))
    )
    (net (code "71") (name "/V12") (class "Default")
      (node (ref "P18") (pin "1") (pinfunction "1_1") (pintype "passive"))
      (node (ref "U6") (pin "8") (pinfunction "A6_8") (pintype "bidirectional"))
    )
    (net (code "72") (name "/V13") (class "Default")
      (node (ref "P10") (pin "1") (pinfunction "1_1") (pintype "passive"))
      (node (ref "U1") (pin "10") (pinfunction "A8_10") (pintype "bidirectional"))
    )
    (net (code "73") (name "/W8") (class "Default")
      (node (ref "P25") (pin "1") (pinfunction "1_1") (pintype "passive"))
      (node (ref "U11") (pin "3") (pinfunction "A1_3") (pintype "bidirectional"))
    )
    (net (code "74") (name "/W13") (class "Default")
      (node (ref "P17") (pin "1") (pinfunction "1_1") (pintype "passive"))
      (node (ref "U6") (pin "7") (pinfunction "A5_7") (pintype "bidirectional"))
    )
    (net (code "75") (name "/W14") (class "Default")
      (node (ref "P15") (pin "1") (pinfunction "1_1") (pintype "passive"))
      (node (ref "U6") (pin "5") (pinfunction "A3_5") (pintype "bidirectional"))
    )
    (net (code "76") (name "/Y6") (class "Default")
      (node (ref "P27") (pin "1") (pinfunction "1_1") (pintype "passive"))
      (node (ref "U11") (pin "5") (pinfunction "A3_5") (pintype "bidirectional"))
    )
    (net (code "77") (name "/Y7") (class "Default")
      (node (ref "P28") (pin "1") (pinfunction "1_1") (pintype "passive"))
      (node (ref "U11") (pin "6") (pinfunction "A4_6") (pintype "bidirectional"))
    )
    (net (code "78") (name "/Y8") (class "Default")
      (node (ref "P2") (pin "1") (pinfunction "1_1") (pintype "passive"))
      (node (ref "U1") (pin "4") (pinfunction "A2_4") (pintype "bidirectional"))
    )
    (net (code "79") (name "/Y9") (class "Default")
      (node (ref "P1") (pin "1") (pinfunction "1_1") (pintype "passive"))
      (node (ref "U1") (pin "3") (pinfunction "A1_3") (pintype "bidirectional"))
    )
    (net (code "80") (name "/Y14") (class "Default")
      (node (ref "P14") (pin "1") (pinfunction "1_1") (pintype "passive"))
      (node (ref "U6") (pin "4") (pinfunction "A2_4") (pintype "bidirectional"))
    )
    (net (code "81") (name "GND") (class "Default")
      (node (ref "C1") (pin "1") (pinfunction "1_1") (pintype "passive"))
      (node (ref "C2") (pin "1") (pinfunction "1_1") (pintype "passive"))
      (node (ref "C3") (pin "2") (pinfunction "2_2") (pintype "passive"))
      (node (ref "C4") (pin "2") (pinfunction "2_2") (pintype "passive"))
      (node (ref "P44") (pin "1") (pinfunction "1_1") (pintype "passive"))
      (node (ref "P46") (pin "1") (pinfunction "1_1") (pintype "passive"))
      (node (ref "P48") (pin "1") (pinfunction "1_1") (pintype "passive"))
      (node (ref "P50") (pin "1") (pinfunction "1_1") (pintype "passive"))
      (node (ref "P51") (pin "1") (pinfunction "1_1") (pintype "passive"))
      (node (ref "P52") (pin "1") (pinfunction "1_1") (pintype "passive"))
      (node (ref "P53") (pin "1") (pinfunction "1_1") (pintype "passive"))
      (node (ref "P54") (pin "1") (pinfunction "1_1") (pintype "passive"))
      (node (ref "P55") (pin "1") (pinfunction "1_1") (pintype "passive"))
      (node (ref "P56") (pin "1") (pinfunction "1_1") (pintype "passive"))
      (node (ref "P57") (pin "1") (pinfunction "1_1") (pintype "passive"))
      (node (ref "P58") (pin "1") (pinfunction "1_1") (pintype "passive"))
      (node (ref "P59") (pin "3") (pinfunction "3_3") (pintype "passive"))
      (node (ref "PD1") (pin "10") (pinfunction "10_10") (pintype "passive"))
      (node (ref "PD1") (pin "9") (pinfunction "9_9") (pintype "passive"))
      (node (ref "PF1") (pin "2") (pinfunction "2_2") (pintype "passive"))
      (node (ref "PF1") (pin "24") (pinfunction "24_24") (pintype "passive"))
      (node (ref "PF1") (pin "25") (pinfunction "25_25") (pintype "passive"))
      (node (ref "PF1") (pin "34") (pinfunction "34_34") (pintype "passive"))
      (node (ref "PF1") (pin "35") (pinfunction "35_35") (pintype "passive"))
      (node (ref "PF1") (pin "4") (pinfunction "4_4") (pintype "passive"))
      (node (ref "PF1") (pin "44") (pinfunction "44_44") (pintype "passive"))
      (node (ref "PF1") (pin "54") (pinfunction "54_54") (pintype "passive"))
      (node (ref "PF1") (pin "67") (pinfunction "67_67") (pintype "passive"))
      (node (ref "PF1") (pin "68") (pinfunction "68_68") (pintype "passive"))
      (node (ref "PF2") (pin "10") (pinfunction "10_10") (pintype "passive"))
      (node (ref "PF2") (pin "2") (pinfunction "2_2") (pintype "passive"))
      (node (ref "PF2") (pin "20") (pinfunction "20_20") (pintype "passive"))
      (node (ref "PF2") (pin "30") (pinfunction "30_30") (pintype "passive"))
      (node (ref "PF2") (pin "4") (pinfunction "4_4") (pintype "passive"))
      (node (ref "PF2") (pin "40") (pinfunction "40_40") (pintype "passive"))
      (node (ref "PF2") (pin "50") (pinfunction "50_50") (pintype "passive"))
      (node (ref "PF2") (pin "60") (pinfunction "60_60") (pintype "passive"))
      (node (ref "PF2") (pin "80") (pinfunction "80_80") (pintype "passive"))
      (node (ref "R3") (pin "1") (pinfunction "1_1") (pintype "passive"))
      (node (ref "R6") (pin "1") (pinfunction "1_1") (pintype "passive"))
      (node (ref "U1") (pin "11") (pinfunction "GND_11") (pintype "power_in"))
      (node (ref "U1") (pin "12") (pinfunction "GND_12") (pintype "power_in"))
      (node (ref "U1") (pin "13") (pinfunction "GND_13") (pintype "power_in"))
      (node (ref "U1") (pin "2") (pinfunction "DIR_2") (pintype "input"))
      (node (ref "U1") (pin "22") (pinfunction "~{OE}_22") (pintype "input"))
      (node (ref "U10") (pin "2") (pinfunction "K_2") (pintype "passive"))
      (node (ref "U10") (pin "3") (pinfunction "E_3") (pintype "passive"))
      (node (ref "U11") (pin "11") (pinfunction "GND_11") (pintype "power_in"))
      (node (ref "U11") (pin "12") (pinfunction "GND_12") (pintype "power_in"))
      (node (ref "U11") (pin "13") (pinfunction "GND_13") (pintype "power_in"))
      (node (ref "U11") (pin "2") (pinfunction "DIR_2") (pintype "input"))
      (node (ref "U11") (pin "22") (pinfunction "~{OE}_22") (pintype "input"))
      (node (ref "U12") (pin "5") (pinfunction "GND_5") (pintype "power_in"))
      (node (ref "U13") (pin "11") (pinfunction "GND_11") (pintype "power_in"))
      (node (ref "U13") (pin "12") (pinfunction "GND_12") (pintype "power_in"))
      (node (ref "U13") (pin "13") (pinfunction "GND_13") (pintype "power_in"))
      (node (ref "U13") (pin "2") (pinfunction "DIR_2") (pintype "input"))
      (node (ref "U13") (pin "22") (pinfunction "~{OE}_22") (pintype "input"))
      (node (ref "U14") (pin "5") (pinfunction "GND_5") (pintype "power_in"))
      (node (ref "U15") (pin "11") (pinfunction "GND_11") (pintype "power_in"))
      (node (ref "U15") (pin "12") (pinfunction "GND_12") (pintype "power_in"))
      (node (ref "U15") (pin "13") (pinfunction "GND_13") (pintype "power_in"))
      (node (ref "U15") (pin "22") (pinfunction "~{OE}_22") (pintype "input"))
      (node (ref "U2") (pin "2") (pinfunction "K_2") (pintype "passive"))
      (node (ref "U2") (pin "3") (pinfunction "E_3") (pintype "passive"))
      (node (ref "U3") (pin "2") (pinfunction "K_2") (pintype "passive"))
      (node (ref "U3") (pin "3") (pinfunction "E_3") (pintype "passive"))
      (node (ref "U4") (pin "2") (pinfunction "K_2") (pintype "passive"))
      (node (ref "U4") (pin "3") (pinfunction "E_3") (pintype "passive"))
      (node (ref "U5") (pin "2") (pinfunction "K_2") (pintype "passive"))
      (node (ref "U5") (pin "3") (pinfunction "E_3") (pintype "passive"))
      (node (ref "U6") (pin "11") (pinfunction "GND_11") (pintype "power_in"))
      (node (ref "U6") (pin "12") (pinfunction "GND_12") (pintype "power_in"))
      (node (ref "U6") (pin "13") (pinfunction "GND_13") (pintype "power_in"))
      (node (ref "U6") (pin "2") (pinfunction "DIR_2") (pintype "input"))
      (node (ref "U6") (pin "22") (pinfunction "~{OE}_22") (pintype "input"))
      (node (ref "U7") (pin "2") (pinfunction "K_2") (pintype "passive"))
      (node (ref "U7") (pin "3") (pinfunction "E_3") (pintype "passive"))
      (node (ref "U8") (pin "2") (pinfunction "K_2") (pintype "passive"))
      (node (ref "U8") (pin "3") (pinfunction "E_3") (pintype "passive"))
      (node (ref "U9") (pin "2") (pinfunction "K_2") (pintype "passive"))
      (node (ref "U9") (pin "3") (pinfunction "E_3") (pintype "passive"))
    )
    (net (code "82") (name "Net-(U1-B1)") (class "Default")
      (node (ref "PF1") (pin "16") (pinfunction "16_16") (pintype "passive"))
      (node (ref "U1") (pin "21") (pinfunction "B1_21") (pintype "bidirectional"))
    )
    (net (code "83") (name "Net-(U1-B2)") (class "Default")
      (node (ref "PF1") (pin "18") (pinfunction "18_18") (pintype "passive"))
      (node (ref "U1") (pin "20") (pinfunction "B2_20") (pintype "bidirectional"))
    )
    (net (code "84") (name "Net-(U1-B3)") (class "Default")
      (node (ref "PF1") (pin "20") (pinfunction "20_20") (pintype "passive"))
      (node (ref "U1") (pin "19") (pinfunction "B3_19") (pintype "bidirectional"))
    )
    (net (code "85") (name "Net-(U1-B4)") (class "Default")
      (node (ref "PF1") (pin "22") (pinfunction "22_22") (pintype "passive"))
      (node (ref "U1") (pin "18") (pinfunction "B4_18") (pintype "bidirectional"))
    )
    (net (code "86") (name "Net-(U1-B5)") (class "Default")
      (node (ref "PF1") (pin "26") (pinfunction "26_26") (pintype "passive"))
      (node (ref "U1") (pin "17") (pinfunction "B5_17") (pintype "bidirectional"))
    )
    (net (code "87") (name "Net-(U1-B6)") (class "Default")
      (node (ref "PF1") (pin "28") (pinfunction "28_28") (pintype "passive"))
      (node (ref "U1") (pin "16") (pinfunction "B6_16") (pintype "bidirectional"))
    )
    (net (code "88") (name "Net-(U1-B7)") (class "Default")
      (node (ref "PF1") (pin "30") (pinfunction "30_30") (pintype "passive"))
      (node (ref "U1") (pin "15") (pinfunction "B7_15") (pintype "bidirectional"))
    )
    (net (code "89") (name "Net-(U1-B8)") (class "Default")
      (node (ref "PF1") (pin "32") (pinfunction "32_32") (pintype "passive"))
      (node (ref "U1") (pin "14") (pinfunction "B8_14") (pintype "bidirectional"))
    )
    (net (code "90") (name "Net-(U2-A)") (class "Default")
      (node (ref "RP3") (pin "1") (pinfunction "1_1") (pintype "passive"))
      (node (ref "U2") (pin "1") (pinfunction "A_1") (pintype "passive"))
    )
    (net (code "91") (name "Net-(U3-A)") (class "Default")
      (node (ref "RP3") (pin "2") (pinfunction "2_2") (pintype "passive"))
      (node (ref "U3") (pin "1") (pinfunction "A_1") (pintype "passive"))
    )
    (net (code "92") (name "Net-(U4-A)") (class "Default")
      (node (ref "RP3") (pin "3") (pinfunction "3_3") (pintype "passive"))
      (node (ref "U4") (pin "1") (pinfunction "A_1") (pintype "passive"))
    )
    (net (code "93") (name "Net-(U5-A)") (class "Default")
      (node (ref "RP3") (pin "4") (pinfunction "4_4") (pintype "passive"))
      (node (ref "U5") (pin "1") (pinfunction "A_1") (pintype "passive"))
    )
    (net (code "94") (name "Net-(U6-B1)") (class "Default")
      (node (ref "PF1") (pin "47") (pinfunction "47_47") (pintype "passive"))
      (node (ref "U6") (pin "21") (pinfunction "B1_21") (pintype "bidirectional"))
    )
    (net (code "95") (name "Net-(U6-B2)") (class "Default")
      (node (ref "PF1") (pin "43") (pinfunction "43_43") (pintype "passive"))
      (node (ref "U6") (pin "20") (pinfunction "B2_20") (pintype "bidirectional"))
    )
    (net (code "96") (name "Net-(U6-B3)") (class "Default")
      (node (ref "PF1") (pin "41") (pinfunction "41_41") (pintype "passive"))
      (node (ref "U6") (pin "19") (pinfunction "B3_19") (pintype "bidirectional"))
    )
    (net (code "97") (name "Net-(U6-B4)") (class "Default")
      (node (ref "PF1") (pin "37") (pinfunction "37_37") (pintype "passive"))
      (node (ref "U6") (pin "18") (pinfunction "B4_18") (pintype "bidirectional"))
    )
    (net (code "98") (name "Net-(U6-B5)") (class "Default")
      (node (ref "PF1") (pin "33") (pinfunction "33_33") (pintype "passive"))
      (node (ref "U6") (pin "17") (pinfunction "B5_17") (pintype "bidirectional"))
    )
    (net (code "99") (name "Net-(U6-B6)") (class "Default")
      (node (ref "PF1") (pin "31") (pinfunction "31_31") (pintype "passive"))
      (node (ref "U6") (pin "16") (pinfunction "B6_16") (pintype "bidirectional"))
    )
    (net (code "100") (name "Net-(U6-B7)") (class "Default")
      (node (ref "PF1") (pin "29") (pinfunction "29_29") (pintype "passive"))
      (node (ref "U6") (pin "15") (pinfunction "B7_15") (pintype "bidirectional"))
    )
    (net (code "101") (name "Net-(U6-B8)") (class "Default")
      (node (ref "PF1") (pin "27") (pinfunction "27_27") (pintype "passive"))
      (node (ref "U6") (pin "14") (pinfunction "B8_14") (pintype "bidirectional"))
    )
    (net (code "102") (name "Net-(U7-A)") (class "Default")
      (node (ref "RP4") (pin "1") (pinfunction "1_1") (pintype "passive"))
      (node (ref "U7") (pin "1") (pinfunction "A_1") (pintype "passive"))
    )
    (net (code "103") (name "Net-(U8-A)") (class "Default")
      (node (ref "RP4") (pin "2") (pinfunction "2_2") (pintype "passive"))
      (node (ref "U8") (pin "1") (pinfunction "A_1") (pintype "passive"))
    )
    (net (code "104") (name "Net-(U9-A)") (class "Default")
      (node (ref "RP4") (pin "3") (pinfunction "3_3") (pintype "passive"))
      (node (ref "U9") (pin "1") (pinfunction "A_1") (pintype "passive"))
    )
    (net (code "105") (name "Net-(U10-A)") (class "Default")
      (node (ref "RP4") (pin "4") (pinfunction "4_4") (pintype "passive"))
      (node (ref "U10") (pin "1") (pinfunction "A_1") (pintype "passive"))
    )
    (net (code "106") (name "Net-(U11-B1)") (class "Default")
      (node (ref "PF1") (pin "23") (pinfunction "23_23") (pintype "passive"))
      (node (ref "U11") (pin "21") (pinfunction "B1_21") (pintype "bidirectional"))
    )
    (net (code "107") (name "Net-(U11-B2)") (class "Default")
      (node (ref "PF1") (pin "21") (pinfunction "21_21") (pintype "passive"))
      (node (ref "U11") (pin "20") (pinfunction "B2_20") (pintype "bidirectional"))
    )
    (net (code "108") (name "Net-(U11-B3)") (class "Default")
      (node (ref "PF1") (pin "19") (pinfunction "19_19") (pintype "passive"))
      (node (ref "U11") (pin "19") (pinfunction "B3_19") (pintype "bidirectional"))
    )
    (net (code "109") (name "Net-(U11-B4)") (class "Default")
      (node (ref "PF1") (pin "17") (pinfunction "17_17") (pintype "passive"))
      (node (ref "U11") (pin "18") (pinfunction "B4_18") (pintype "bidirectional"))
    )
    (net (code "110") (name "Net-(U11-B5)") (class "Default")
      (node (ref "PF1") (pin "13") (pinfunction "13_13") (pintype "passive"))
      (node (ref "U11") (pin "17") (pinfunction "B5_17") (pintype "bidirectional"))
    )
    (net (code "111") (name "Net-(U11-B6)") (class "Default")
      (node (ref "PF1") (pin "11") (pinfunction "11_11") (pintype "passive"))
      (node (ref "U11") (pin "16") (pinfunction "B6_16") (pintype "bidirectional"))
    )
    (net (code "112") (name "Net-(U11-B7)") (class "Default")
      (node (ref "PF1") (pin "9") (pinfunction "9_9") (pintype "passive"))
      (node (ref "U11") (pin "15") (pinfunction "B7_15") (pintype "bidirectional"))
    )
    (net (code "113") (name "Net-(U11-B8)") (class "Default")
      (node (ref "PF1") (pin "7") (pinfunction "7_7") (pintype "passive"))
      (node (ref "U11") (pin "14") (pinfunction "B8_14") (pintype "bidirectional"))
    )
    (net (code "114") (name "Net-(U13-B1)") (class "Default")
      (node (ref "PF2") (pin "42") (pinfunction "42_42") (pintype "passive"))
      (node (ref "U13") (pin "21") (pinfunction "B1_21") (pintype "bidirectional"))
    )
    (net (code "115") (name "Net-(U13-B2)") (class "Default")
      (node (ref "PF2") (pin "44") (pinfunction "44_44") (pintype "passive"))
      (node (ref "U13") (pin "20") (pinfunction "B2_20") (pintype "bidirectional"))
    )
    (net (code "116") (name "Net-(U13-B3)") (class "Default")
      (node (ref "PF2") (pin "46") (pinfunction "46_46") (pintype "passive"))
      (node (ref "U13") (pin "19") (pinfunction "B3_19") (pintype "bidirectional"))
    )
    (net (code "117") (name "Net-(U13-B4)") (class "Default")
      (node (ref "PF2") (pin "48") (pinfunction "48_48") (pintype "passive"))
      (node (ref "U13") (pin "18") (pinfunction "B4_18") (pintype "bidirectional"))
    )
    (net (code "118") (name "Net-(U13-B5)") (class "Default")
      (node (ref "PF2") (pin "52") (pinfunction "52_52") (pintype "passive"))
      (node (ref "U13") (pin "17") (pinfunction "B5_17") (pintype "bidirectional"))
    )
    (net (code "119") (name "Net-(U13-B6)") (class "Default")
      (node (ref "PF2") (pin "54") (pinfunction "54_54") (pintype "passive"))
      (node (ref "U13") (pin "16") (pinfunction "B6_16") (pintype "bidirectional"))
    )
    (net (code "120") (name "Net-(U13-B7)") (class "Default")
      (node (ref "PF2") (pin "56") (pinfunction "56_56") (pintype "passive"))
      (node (ref "U13") (pin "15") (pinfunction "B7_15") (pintype "bidirectional"))
    )
    (net (code "121") (name "Net-(U13-B8)") (class "Default")
      (node (ref "PF2") (pin "58") (pinfunction "58_58") (pintype "passive"))
      (node (ref "U13") (pin "14") (pinfunction "B8_14") (pintype "bidirectional"))
    )
    (net (code "122") (name "Net-(U15-B1)") (class "Default")
      (node (ref "PF2") (pin "62") (pinfunction "62_62") (pintype "passive"))
      (node (ref "U15") (pin "21") (pinfunction "B1_21") (pintype "bidirectional"))
    )
    (net (code "123") (name "Net-(U15-B2)") (class "Default")
      (node (ref "PF2") (pin "64") (pinfunction "64_64") (pintype "passive"))
      (node (ref "U15") (pin "20") (pinfunction "B2_20") (pintype "bidirectional"))
    )
    (net (code "124") (name "Net-(U15-B3)") (class "Default")
      (node (ref "PF2") (pin "66") (pinfunction "66_66") (pintype "passive"))
      (node (ref "U15") (pin "19") (pinfunction "B3_19") (pintype "bidirectional"))
    )
    (net (code "125") (name "Net-(U15-B4)") (class "Default")
      (node (ref "PF2") (pin "68") (pinfunction "68_68") (pintype "passive"))
      (node (ref "U15") (pin "18") (pinfunction "B4_18") (pintype "bidirectional"))
    )
    (net (code "126") (name "Net-(U15-B5)") (class "Default")
      (node (ref "PF2") (pin "72") (pinfunction "72_72") (pintype "passive"))
      (node (ref "U15") (pin "17") (pinfunction "B5_17") (pintype "bidirectional"))
    )
    (net (code "127") (name "Net-(U15-B6)") (class "Default")
      (node (ref "PF2") (pin "74") (pinfunction "74_74") (pintype "passive"))
      (node (ref "U15") (pin "16") (pinfunction "B6_16") (pintype "bidirectional"))
    )
    (net (code "128") (name "unconnected-(E1-A-Pad1)") (class "Default")
      (node (ref "E1") (pin "1") (pinfunction "A_1") (pintype "passive"))
    )
    (net (code "129") (name "unconnected-(E2-A-Pad1)") (class "Default")
      (node (ref "E2") (pin "1") (pinfunction "A_1") (pintype "passive"))
    )
    (net (code "130") (name "unconnected-(E3-A-Pad1)") (class "Default")
      (node (ref "E3") (pin "1") (pinfunction "A_1") (pintype "passive"))
    )
    (net (code "131") (name "unconnected-(E4-A-Pad1)") (class "Default")
      (node (ref "E4") (pin "1") (pinfunction "A_1") (pintype "passive"))
    )
    (net (code "132") (name "unconnected-(E5-A-Pad1)") (class "Default")
      (node (ref "E5") (pin "1") (pinfunction "A_1") (pintype "passive"))
    )
    (net (code "133") (name "unconnected-(E6-A-Pad1)") (class "Default")
      (node (ref "E6") (pin "1") (pinfunction "A_1") (pintype "passive"))
    )
    (net (code "134") (name "unconnected-(E7-A-Pad1)") (class "Default")
      (node (ref "E7") (pin "1") (pinfunction "A_1") (pintype "passive"))
    )
    (net (code "135") (name "unconnected-(PF1-Pad3)") (class "Default")
      (node (ref "PF1") (pin "3") (pinfunction "3_3") (pintype "passive"))
    )
    (net (code "136") (name "unconnected-(PF1-Pad5)") (class "Default")
      (node (ref "PF1") (pin "5") (pinfunction "5_5") (pintype "passive"))
    )
    (net (code "137") (name "unconnected-(PF1-Pad6)") (class "Default")
      (node (ref "PF1") (pin "6") (pinfunction "6_6") (pintype "passive"))
    )
    (net (code "138") (name "unconnected-(PF1-Pad8)") (class "Default")
      (node (ref "PF1") (pin "8") (pinfunction "8_8") (pintype "passive"))
    )
    (net (code "139") (name "unconnected-(PF1-Pad10)") (class "Default")
      (node (ref "PF1") (pin "10") (pinfunction "10_10") (pintype "passive"))
    )
    (net (code "140") (name "unconnected-(PF1-Pad12)") (class "Default")
      (node (ref "PF1") (pin "12") (pinfunction "12_12") (pintype "passive"))
    )
    (net (code "141") (name "unconnected-(PF1-Pad14)") (class "Default")
      (node (ref "PF1") (pin "14") (pinfunction "14_14") (pintype "passive"))
    )
    (net (code "142") (name "unconnected-(PF1-Pad15)") (class "Default")
      (node (ref "PF1") (pin "15") (pinfunction "15_15") (pintype "passive"))
    )
    (net (code "143") (name "unconnected-(PF1-Pad36)") (class "Default")
      (node (ref "PF1") (pin "36") (pinfunction "36_36") (pintype "passive"))
    )
    (net (code "144") (name "unconnected-(PF1-Pad38)") (class "Default")
      (node (ref "PF1") (pin "38") (pinfunction "38_38") (pintype "passive"))
    )
    (net (code "145") (name "unconnected-(PF1-Pad39)") (class "Default")
      (node (ref "PF1") (pin "39") (pinfunction "39_39") (pintype "passive"))
    )
    (net (code "146") (name "unconnected-(PF1-Pad40)") (class "Default")
      (node (ref "PF1") (pin "40") (pinfunction "40_40") (pintype "passive"))
    )
    (net (code "147") (name "unconnected-(PF1-Pad42)") (class "Default")
      (node (ref "PF1") (pin "42") (pinfunction "42_42") (pintype "passive"))
    )
    (net (code "148") (name "unconnected-(PF1-Pad45)") (class "Default")
      (node (ref "PF1") (pin "45") (pinfunction "45_45") (pintype "passive"))
    )
    (net (code "149") (name "unconnected-(PF1-Pad46)") (class "Default")
      (node (ref "PF1") (pin "46") (pinfunction "46_46") (pintype "passive"))
    )
    (net (code "150") (name "unconnected-(PF1-Pad48)") (class "Default")
      (node (ref "PF1") (pin "48") (pinfunction "48_48") (pintype "passive"))
    )
    (net (code "151") (name "unconnected-(PF1-Pad49)") (class "Default")
      (node (ref "PF1") (pin "49") (pinfunction "49_49") (pintype "passive"))
    )
    (net (code "152") (name "unconnected-(PF1-Pad50)") (class "Default")
      (node (ref "PF1") (pin "50") (pinfunction "50_50") (pintype "passive"))
    )
    (net (code "153") (name "unconnected-(PF1-Pad51)") (class "Default")
      (node (ref "PF1") (pin "51") (pinfunction "51_51") (pintype "passive"))
    )
    (net (code "154") (name "unconnected-(PF1-Pad52)") (class "Default")
      (node (ref "PF1") (pin "52") (pinfunction "52_52") (pintype "passive"))
    )
    (net (code "155") (name "unconnected-(PF1-Pad53)") (class "Default")
      (node (ref "PF1") (pin "53") (pinfunction "53_53") (pintype "passive"))
    )
    (net (code "156") (name "unconnected-(PF1-Pad55)") (class "Default")
      (node (ref "PF1") (pin "55") (pinfunction "55_55") (pintype "passive"))
    )
    (net (code "157") (name "unconnected-(PF1-Pad56)") (class "Default")
      (node (ref "PF1") (pin "56") (pinfunction "56_56") (pintype "passive"))
    )
    (net (code "158") (name "unconnected-(PF1-Pad57)") (class "Default")
      (node (ref "PF1") (pin "57") (pinfunction "57_57") (pintype "passive"))
    )
    (net (code "159") (name "unconnected-(PF1-Pad58)") (class "Default")
      (node (ref "PF1") (pin "58") (pinfunction "58_58") (pintype "passive"))
    )
    (net (code "160") (name "unconnected-(PF1-Pad59)") (class "Default")
      (node (ref "PF1") (pin "59") (pinfunction "59_59") (pintype "passive"))
    )
    (net (code "161") (name "unconnected-(PF1-Pad60)") (class "Default")
      (node (ref "PF1") (pin "60") (pinfunction "60_60") (pintype "passive"))
    )
    (net (code "162") (name "unconnected-(PF1-Pad61)") (class "Default")
      (node (ref "PF1") (pin "61") (pinfunction "61_61") (pintype "passive"))
    )
    (net (code "163") (name "unconnected-(PF1-Pad62)") (class "Default")
      (node (ref "PF1") (pin "62") (pinfunction "62_62") (pintype "passive"))
    )
    (net (code "164") (name "unconnected-(PF1-Pad63)") (class "Default")
      (node (ref "PF1") (pin "63") (pinfunction "63_63") (pintype "passive"))
    )
    (net (code "165") (name "unconnected-(PF1-Pad64)") (class "Default")
      (node (ref "PF1") (pin "64") (pinfunction "64_64") (pintype "passive"))
    )
    (net (code "166") (name "unconnected-(PF1-Pad65)") (class "Default")
      (node (ref "PF1") (pin "65") (pinfunction "65_65") (pintype "passive"))
    )
    (net (code "167") (name "unconnected-(PF1-Pad66)") (class "Default")
      (node (ref "PF1") (pin "66") (pinfunction "66_66") (pintype "passive"))
    )
    (net (code "168") (name "unconnected-(PF1-Pad69)") (class "Default")
      (node (ref "PF1") (pin "69") (pinfunction "69_69") (pintype "passive"))
    )
    (net (code "169") (name "unconnected-(PF1-Pad70)") (class "Default")
      (node (ref "PF1") (pin "70") (pinfunction "70_70") (pintype "passive"))
    )
    (net (code "170") (name "unconnected-(PF1-Pad71)") (class "Default")
      (node (ref "PF1") (pin "71") (pinfunction "71_71") (pintype "passive"))
    )
    (net (code "171") (name "unconnected-(PF1-Pad72)") (class "Default")
      (node (ref "PF1") (pin "72") (pinfunction "72_72") (pintype "passive"))
    )
    (net (code "172") (name "unconnected-(PF1-Pad73)") (class "Default")
      (node (ref "PF1") (pin "73") (pinfunction "73_73") (pintype "passive"))
    )
    (net (code "173") (name "unconnected-(PF1-Pad74)") (class "Default")
      (node (ref "PF1") (pin "74") (pinfunction "74_74") (pintype "passive"))
    )
    (net (code "174") (name "unconnected-(PF1-Pad75)") (class "Default")
      (node (ref "PF1") (pin "75") (pinfunction "75_75") (pintype "passive"))
    )
    (net (code "175") (name "unconnected-(PF1-Pad76)") (class "Default")
      (node (ref "PF1") (pin "76") (pinfunction "76_76") (pintype "passive"))
    )
    (net (code "176") (name "unconnected-(PF1-Pad77)") (class "Default")
      (node (ref "PF1") (pin "77") (pinfunction "77_77") (pintype "passive"))
    )
    (net (code "177") (name "unconnected-(PF1-Pad78)") (class "Default")
      (node (ref "PF1") (pin "78") (pinfunction "78_78") (pintype "passive"))
    )
    (net (code "178") (name "unconnected-(PF1-Pad79)") (class "Default")
      (node (ref "PF1") (pin "79") (pinfunction "79_79") (pintype "passive"))
    )
    (net (code "179") (name "unconnected-(PF1-Pad80)") (class "Default")
      (node (ref "PF1") (pin "80") (pinfunction "80_80") (pintype "passive"))
    )
    (net (code "180") (name "unconnected-(PF2-Pad3)") (class "Default")
      (node (ref "PF2") (pin "3") (pinfunction "3_3") (pintype "passive"))
    )
    (net (code "181") (name "unconnected-(PF2-Pad5)") (class "Default")
      (node (ref "PF2") (pin "5") (pinfunction "5_5") (pintype "passive"))
    )
    (net (code "182") (name "unconnected-(PF2-Pad6)") (class "Default")
      (node (ref "PF2") (pin "6") (pinfunction "6_6") (pintype "passive"))
    )
    (net (code "183") (name "unconnected-(PF2-Pad7)") (class "Default")
      (node (ref "PF2") (pin "7") (pinfunction "7_7") (pintype "passive"))
    )
    (net (code "184") (name "unconnected-(PF2-Pad8)") (class "Default")
      (node (ref "PF2") (pin "8") (pinfunction "8_8") (pintype "passive"))
    )
    (net (code "185") (name "unconnected-(PF2-Pad9)") (class "Default")
      (node (ref "PF2") (pin "9") (pinfunction "9_9") (pintype "passive"))
    )
    (net (code "186") (name "unconnected-(PF2-Pad11)") (class "Default")
      (node (ref "PF2") (pin "11") (pinfunction "11_11") (pintype "passive"))
    )
    (net (code "187") (name "unconnected-(PF2-Pad12)") (class "Default")
      (node (ref "PF2") (pin "12") (pinfunction "12_12") (pintype "passive"))
    )
    (net (code "188") (name "unconnected-(PF2-Pad13)") (class "Default")
      (node (ref "PF2") (pin "13") (pinfunction "13_13") (pintype "passive"))
    )
    (net (code "189") (name "unconnected-(PF2-Pad14)") (class "Default")
      (node (ref "PF2") (pin "14") (pinfunction "14_14") (pintype "passive"))
    )
    (net (code "190") (name "unconnected-(PF2-Pad15)") (class "Default")
      (node (ref "PF2") (pin "15") (pinfunction "15_15") (pintype "passive"))
    )
    (net (code "191") (name "unconnected-(PF2-Pad16)") (class "Default")
      (node (ref "PF2") (pin "16") (pinfunction "16_16") (pintype "passive"))
    )
    (net (code "192") (name "unconnected-(PF2-Pad17)") (class "Default")
      (node (ref "PF2") (pin "17") (pinfunction "17_17") (pintype "passive"))
    )
    (net (code "193") (name "unconnected-(PF2-Pad18)") (class "Default")
      (node (ref "PF2") (pin "18") (pinfunction "18_18") (pintype "passive"))
    )
    (net (code "194") (name "unconnected-(PF2-Pad19)") (class "Default")
      (node (ref "PF2") (pin "19") (pinfunction "19_19") (pintype "passive"))
    )
    (net (code "195") (name "unconnected-(PF2-Pad21)") (class "Default")
      (node (ref "PF2") (pin "21") (pinfunction "21_21") (pintype "passive"))
    )
    (net (code "196") (name "unconnected-(PF2-Pad23)") (class "Default")
      (node (ref "PF2") (pin "23") (pinfunction "23_23") (pintype "passive"))
    )
    (net (code "197") (name "unconnected-(PF2-Pad25)") (class "Default")
      (node (ref "PF2") (pin "25") (pinfunction "25_25") (pintype "passive"))
    )
    (net (code "198") (name "unconnected-(PF2-Pad27)") (class "Default")
      (node (ref "PF2") (pin "27") (pinfunction "27_27") (pintype "passive"))
    )
    (net (code "199") (name "unconnected-(PF2-Pad29)") (class "Default")
      (node (ref "PF2") (pin "29") (pinfunction "29_29") (pintype "passive"))
    )
    (net (code "200") (name "unconnected-(PF2-Pad31)") (class "Default")
      (node (ref "PF2") (pin "31") (pinfunction "31_31") (pintype "passive"))
    )
    (net (code "201") (name "unconnected-(PF2-Pad33)") (class "Default")
      (node (ref "PF2") (pin "33") (pinfunction "33_33") (pintype "passive"))
    )
    (net (code "202") (name "unconnected-(PF2-Pad35)") (class "Default")
      (node (ref "PF2") (pin "35") (pinfunction "35_35") (pintype "passive"))
    )
    (net (code "203") (name "unconnected-(PF2-Pad37)") (class "Default")
      (node (ref "PF2") (pin "37") (pinfunction "37_37") (pintype "passive"))
    )
    (net (code "204") (name "unconnected-(PF2-Pad39)") (class "Default")
      (node (ref "PF2") (pin "39") (pinfunction "39_39") (pintype "passive"))
    )
    (net (code "205") (name "unconnected-(PF2-Pad41)") (class "Default")
      (node (ref "PF2") (pin "41") (pinfunction "41_41") (pintype "passive"))
    )
    (net (code "206") (name "unconnected-(PF2-Pad51)") (class "Default")
      (node (ref "PF2") (pin "51") (pinfunction "51_51") (pintype "passive"))
    )
    (net (code "207") (name "unconnected-(PF2-Pad61)") (class "Default")
      (node (ref "PF2") (pin "61") (pinfunction "61_61") (pintype "passive"))
    )
    (net (code "208") (name "unconnected-(PF2-Pad70)") (class "Default")
      (node (ref "PF2") (pin "70") (pinfunction "70_70") (pintype "passive"))
    )
    (net (code "209") (name "unconnected-(PF2-Pad71)") (class "Default")
      (node (ref "PF2") (pin "71") (pinfunction "71_71") (pintype "passive"))
    )
  )
)
